# Buck_Converter.net
KiCad netlist of a schematic drawn in Altium Designer
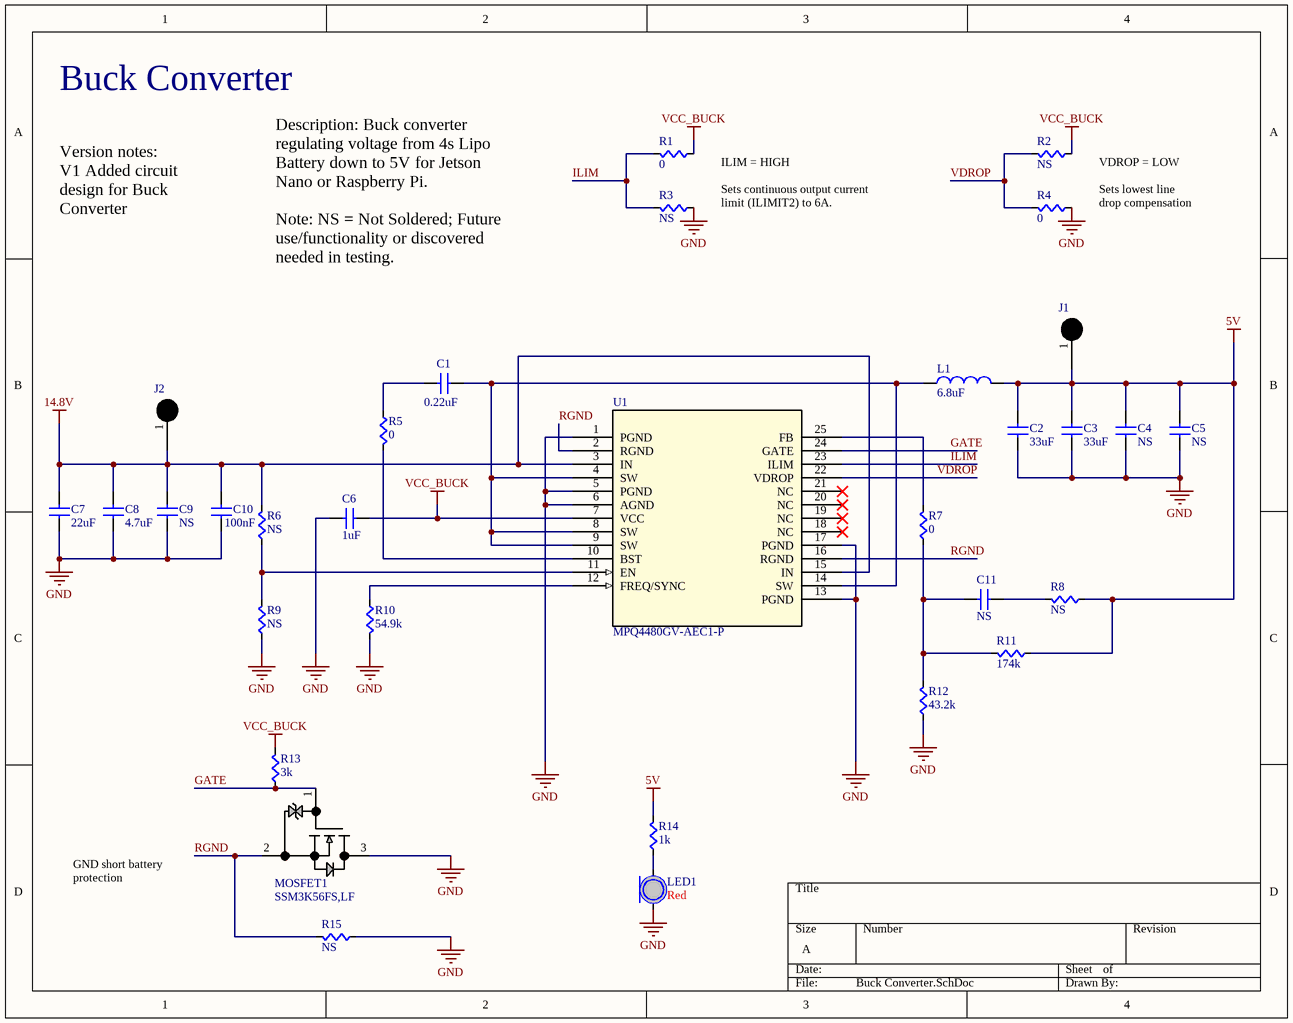
[diagram p0: Buck Converter.SchDoc]

(export (version "E")
  (design (tool "Eeschema 10.0.6"))
  (components
    (comp (ref "C1")
      (value "0.22uF")
      (footprint "CAPC0603")
      (description "0.22 µF ±10% 50V Ceramic Capacitor X7R 0603 (1608 Metric)")
      (fields (field (name "Comment") "C1608X7R1H224K080AE"))
      (libsource (lib "Passives") (part "C1608X7R1H224K080AE"))
    )
    (comp (ref "C2")
      (value "33uF")
      (footprint "CAP1210")
      (description "33 µF ±20% 10V Ceramic Capacitor X5R 1210 (3225 Metric)")
      (fields (field (name "Comment") "C3225X5R1A336M200AC"))
      (libsource (lib "Passives") (part "C3225X5R1A336M200AC"))
    )
    (comp (ref "C3")
      (value "33uF")
      (footprint "CAP1210")
      (description "33 µF ±20% 10V Ceramic Capacitor X5R 1210 (3225 Metric)")
      (fields (field (name "Comment") "C3225X5R1A336M200AC"))
      (libsource (lib "Passives") (part "C3225X5R1A336M200AC"))
    )
    (comp (ref "C4")
      (value "NS")
      (footprint "CAPC1206")
      (fields (field (name "Comment") "Cap"))
      (libsource (lib "Passives") (part "Cap"))
    )
    (comp (ref "C5")
      (value "NS")
      (footprint "CAPC1206")
      (fields (field (name "Comment") "Cap"))
      (libsource (lib "Passives") (part "Cap"))
    )
    (comp (ref "C6")
      (value "1uF")
      (footprint "CAPC0603")
      (description "1 µF ±10% 50V Ceramic Capacitor X5R 0603 (1608 Metric)")
      (fields (field (name "Comment") "CL10A105KB8NNNC"))
      (libsource (lib "Passives") (part "CL10A105KB8NNNC"))
    )
    (comp (ref "C7")
      (value "22uF")
      (footprint "CAPC1206")
      (description "22 µF ±10% 25V Ceramic Capacitor X5R 1206 (3216 Metric)")
      (fields (field (name "Comment") "CL31A226KAHNNNE"))
      (libsource (lib "Passives") (part "CL31A226KAHNNNE"))
    )
    (comp (ref "C8")
      (value "4.7uF")
      (footprint "CAPC1206")
      (description "4.7 µF ±10% 50V Ceramic Capacitor X7R 1206 (3216 Metric)")
      (fields (field (name "Comment") "885012208094"))
      (libsource (lib "Passives") (part "885012208094"))
    )
    (comp (ref "C9")
      (value "NS")
      (footprint "CAPC1206")
      (description "Not Soldered (NS)")
      (fields (field (name "Comment") "Cap"))
      (libsource (lib "Passives") (part "Cap"))
    )
    (comp (ref "C10")
      (value "100nF")
      (footprint "CAPC0603")
      (description "0.1 µF ±10% 50V Ceramic Capacitor X7R 0603 (1608 Metric)")
      (fields (field (name "Comment") "CL10B104KB8NNNC"))
      (libsource (lib "Passives") (part "CL10B104KB8NNNC"))
    )
    (comp (ref "C11")
      (value "NS")
      (footprint "CAPC0603")
      (fields (field (name "Comment") "Cap"))
      (libsource (lib "Passives") (part "Cap"))
    )
    (comp (ref "J1")
      (value "5000 Test Point")
      (footprint "5000 Test Point")
      (libsource (lib "Connectors") (part "5000 Test Point"))
    )
    (comp (ref "J2")
      (value "5000 Test Point")
      (footprint "5000 Test Point")
      (libsource (lib "Connectors") (part "5000 Test Point"))
    )
    (comp (ref "L1")
      (value "SRR1280A-6R8Y")
      (footprint "SRR1208 Series")
      (description "FIXED IND 6.8UH 7.6A 18.5MOHM SM")
      (fields (field (name "INDUCTANCE") "6.8uF"))
      (libsource (lib "Passives") (part "SRR1280A-6R8Y"))
    )
    (comp (ref "LED1")
      (value "LED")
      (footprint "LED1206")
      (fields (field (name "COLOR") "Red"))
      (libsource (lib "Semiconductors") (part "LED"))
    )
    (comp (ref "MOSFET1")
      (value "SSM3K56FS,LF")
      (footprint "SSM_TOS")
      (description "No Description Available")
      (fields (field (name "COPYRIGHT") "Copyright (C) 2023 Ultra Librarian. All rights reserved."))
      (libsource (lib "ICs") (part "SSM3K56FS,LF"))
    )
    (comp (ref "R1")
      (value "0")
      (footprint "RES0603")
      (description "0 Ohms Jumper Chip Resistor 0603 (1608 Metric) Automotive AEC-Q200 Thick Film")
      (fields (field (name "Comment") "RMCF0603ZT0R00"))
      (libsource (lib "Passives") (part "RMCF0603ZT0R00"))
    )
    (comp (ref "R2")
      (value "NS")
      (footprint "RES0603")
      (fields (field (name "Comment") "Res"))
      (libsource (lib "Passives") (part "Res"))
    )
    (comp (ref "R3")
      (value "NS")
      (footprint "RES0603")
      (fields (field (name "Comment") "Res"))
      (libsource (lib "Passives") (part "Res"))
    )
    (comp (ref "R4")
      (value "0")
      (footprint "RES0603")
      (description "0 Ohms Jumper Chip Resistor 0603 (1608 Metric) Automotive AEC-Q200 Thick Film")
      (fields (field (name "Comment") "RMCF0603ZT0R00"))
      (libsource (lib "Passives") (part "RMCF0603ZT0R00"))
    )
    (comp (ref "R5")
      (value "0")
      (footprint "RES0603")
      (description "0 Ohms Jumper Chip Resistor 0603 (1608 Metric) Automotive AEC-Q200 Thick Film")
      (fields (field (name "Comment") "RMCF0603ZT0R00"))
      (libsource (lib "Passives") (part "RMCF0603ZT0R00"))
    )
    (comp (ref "R6")
      (value "NS")
      (footprint "RES0603")
      (fields (field (name "Comment") "Res"))
      (libsource (lib "Passives") (part "Res"))
    )
    (comp (ref "R7")
      (value "0")
      (footprint "RES0603")
      (description "0 Ohms Jumper Chip Resistor 0603 (1608 Metric) Automotive AEC-Q200 Thick Film")
      (fields (field (name "Comment") "RMCF0603ZT0R00"))
      (libsource (lib "Passives") (part "RMCF0603ZT0R00"))
    )
    (comp (ref "R8")
      (value "NS")
      (footprint "RES0603")
      (fields (field (name "Comment") "Res"))
      (libsource (lib "Passives") (part "Res"))
    )
    (comp (ref "R9")
      (value "NS")
      (footprint "RES0603")
      (fields (field (name "Comment") "Res"))
      (libsource (lib "Passives") (part "Res"))
    )
    (comp (ref "R10")
      (value "54.9k")
      (footprint "RES0603")
      (description "54.9 kOhms ±1% 0.1W, 1/10W Chip Resistor 0603 (1608 Metric) Automotive AEC-Q200 Thick Film")
      (fields (field (name "Comment") "RMCF0603FT54K9"))
      (libsource (lib "Passives") (part "RMCF0603FT54K9"))
    )
    (comp (ref "R11")
      (value "174k")
      (footprint "RES0603")
      (description "174 kOhms ±1% 0.1W, 1/10W Chip Resistor 0603 (1608 Metric) Moisture Resistant Thick Film")
      (fields (field (name "Comment") "RC0603FR-07174KL"))
      (libsource (lib "Passives") (part "RC0603FR-07174KL"))
    )
    (comp (ref "R12")
      (value "43.2k")
      (footprint "RES0603")
      (description "43.2 kOhms ±1% 0.1W, 1/10W Chip Resistor 0603 (1608 Metric) Moisture Resistant Thick Film")
      (fields (field (name "Comment") "RC0603FR-0743K2L"))
      (libsource (lib "Passives") (part "RC0603FR-0743K2L"))
    )
    (comp (ref "R13")
      (value "3k")
      (footprint "RES0603")
      (description "3 kOhms ±1% 0.1W, 1/10W Chip Resistor 0603 (1608 Metric) Automotive AEC-Q200 Thick Film")
      (fields (field (name "Comment") "RMCF0603FT3K00"))
      (libsource (lib "Passives") (part "RMCF0603FT3K00"))
    )
    (comp (ref "R14")
      (value "1k")
      (footprint "RES0603")
      (description "1 kOhms ±1% 0.1W, 1/10W Chip Resistor 0603 (1608 Metric) Moisture Resistant Thick Film")
      (fields (field (name "Comment") "RC0603FR-071KL"))
      (libsource (lib "Passives") (part "RC0603FR-071KL"))
    )
    (comp (ref "R15")
      (value "NS")
      (footprint "RES0603")
      (fields (field (name "Comment") "Res"))
      (libsource (lib "Passives") (part "Res"))
    )
    (comp (ref "U1")
      (value "MPQ4480GV-AEC1-P")
      (footprint "QFN-25_4X5_MNP")
      (description "No Description Available")
      (fields (field (name "COPYRIGHT") "Copyright (C) 2023 Ultra Librarian. All rights reserved."))
      (libsource (lib "ICs") (part "MPQ4480GV-AEC1-P"))
    )
  )
  (nets
    (net (code "1") (name "/GATE") (class "Default")
      (node (ref "MOSFET1") (pin "1") (pinfunction "1_1") (pintype "passive"))
      (node (ref "R13") (pin "2") (pinfunction "B_2") (pintype "passive"))
      (node (ref "U1") (pin "24") (pinfunction "GATE_24") (pintype "passive"))
    )
    (net (code "2") (name "/ILIM") (class "Default")
      (node (ref "R1") (pin "1") (pinfunction "A_1") (pintype "passive"))
      (node (ref "R3") (pin "1") (pinfunction "A_1") (pintype "passive"))
      (node (ref "U1") (pin "23") (pinfunction "ILIM_23") (pintype "passive"))
    )
    (net (code "3") (name "/RGND") (class "Default")
      (node (ref "MOSFET1") (pin "2") (pinfunction "2_2") (pintype "passive"))
      (node (ref "R15") (pin "1") (pinfunction "A_1") (pintype "passive"))
      (node (ref "U1") (pin "16") (pinfunction "RGND_16") (pintype "passive"))
      (node (ref "U1") (pin "2") (pinfunction "RGND_2") (pintype "passive"))
    )
    (net (code "4") (name "/VDROP") (class "Default")
      (node (ref "R2") (pin "1") (pinfunction "A_1") (pintype "passive"))
      (node (ref "R4") (pin "1") (pinfunction "A_1") (pintype "passive"))
      (node (ref "U1") (pin "22") (pinfunction "VDROP_22") (pintype "power_in"))
    )
    (net (code "5") (name "5V") (class "Default")
      (node (ref "C2") (pin "1") (pinfunction "A_1") (pintype "passive"))
      (node (ref "C3") (pin "1") (pinfunction "A_1") (pintype "passive"))
      (node (ref "C4") (pin "1") (pinfunction "A_1") (pintype "passive"))
      (node (ref "C5") (pin "1") (pinfunction "A_1") (pintype "passive"))
      (node (ref "J1") (pin "1") (pintype "passive"))
      (node (ref "L1") (pin "2") (pinfunction "B_2") (pintype "passive"))
      (node (ref "R11") (pin "2") (pinfunction "B_2") (pintype "passive"))
      (node (ref "R14") (pin "1") (pinfunction "A_1") (pintype "passive"))
      (node (ref "R8") (pin "2") (pinfunction "B_2") (pintype "passive"))
    )
    (net (code "6") (name "14.8V") (class "Default")
      (node (ref "C10") (pin "1") (pinfunction "A_1") (pintype "passive"))
      (node (ref "C7") (pin "1") (pinfunction "A_1") (pintype "passive"))
      (node (ref "C8") (pin "1") (pinfunction "A_1") (pintype "passive"))
      (node (ref "C9") (pin "1") (pinfunction "A_1") (pintype "passive"))
      (node (ref "J2") (pin "1") (pintype "passive"))
      (node (ref "R6") (pin "1") (pinfunction "A_1") (pintype "passive"))
      (node (ref "U1") (pin "15") (pinfunction "IN_15") (pintype "power_in"))
      (node (ref "U1") (pin "3") (pinfunction "IN_3") (pintype "power_in"))
    )
    (net (code "7") (name "GND") (class "Default")
      (node (ref "C10") (pin "2") (pinfunction "B_2") (pintype "passive"))
      (node (ref "C2") (pin "2") (pinfunction "B_2") (pintype "passive"))
      (node (ref "C3") (pin "2") (pinfunction "B_2") (pintype "passive"))
      (node (ref "C4") (pin "2") (pinfunction "B_2") (pintype "passive"))
      (node (ref "C5") (pin "2") (pinfunction "B_2") (pintype "passive"))
      (node (ref "C6") (pin "2") (pinfunction "B_2") (pintype "passive"))
      (node (ref "C7") (pin "2") (pinfunction "B_2") (pintype "passive"))
      (node (ref "C8") (pin "2") (pinfunction "B_2") (pintype "passive"))
      (node (ref "C9") (pin "2") (pinfunction "B_2") (pintype "passive"))
      (node (ref "LED1") (pin "C") (pinfunction "C_C") (pintype "passive"))
      (node (ref "MOSFET1") (pin "3") (pinfunction "3_3") (pintype "passive"))
      (node (ref "R10") (pin "1") (pinfunction "A_1") (pintype "passive"))
      (node (ref "R12") (pin "2") (pinfunction "B_2") (pintype "passive"))
      (node (ref "R15") (pin "2") (pinfunction "B_2") (pintype "passive"))
      (node (ref "R3") (pin "2") (pinfunction "B_2") (pintype "passive"))
      (node (ref "R4") (pin "2") (pinfunction "B_2") (pintype "passive"))
      (node (ref "R9") (pin "2") (pinfunction "B_2") (pintype "passive"))
      (node (ref "U1") (pin "1") (pinfunction "PGND_1") (pintype "passive"))
      (node (ref "U1") (pin "13") (pinfunction "PGND_13") (pintype "passive"))
      (node (ref "U1") (pin "17") (pinfunction "PGND_17") (pintype "passive"))
      (node (ref "U1") (pin "5") (pinfunction "PGND_5") (pintype "passive"))
      (node (ref "U1") (pin "6") (pinfunction "AGND_6") (pintype "passive"))
    )
    (net (code "8") (name "Net-(C1-A)") (class "Default")
      (node (ref "C1") (pin "1") (pinfunction "A_1") (pintype "passive"))
      (node (ref "R5") (pin "2") (pinfunction "B_2") (pintype "passive"))
    )
    (net (code "9") (name "Net-(C1-B)") (class "Default")
      (node (ref "C1") (pin "2") (pinfunction "B_2") (pintype "passive"))
      (node (ref "L1") (pin "1") (pinfunction "A_1") (pintype "passive"))
      (node (ref "U1") (pin "14") (pinfunction "SW_14") (pintype "passive"))
      (node (ref "U1") (pin "4") (pinfunction "SW_4") (pintype "passive"))
      (node (ref "U1") (pin "8") (pinfunction "SW_8") (pintype "passive"))
      (node (ref "U1") (pin "9") (pinfunction "SW_9") (pintype "passive"))
    )
    (net (code "10") (name "Net-(C11-A)") (class "Default")
      (node (ref "C11") (pin "1") (pinfunction "A_1") (pintype "passive"))
      (node (ref "R11") (pin "1") (pinfunction "A_1") (pintype "passive"))
      (node (ref "R12") (pin "1") (pinfunction "A_1") (pintype "passive"))
      (node (ref "R7") (pin "2") (pinfunction "B_2") (pintype "passive"))
    )
    (net (code "11") (name "Net-(C11-B)") (class "Default")
      (node (ref "C11") (pin "2") (pinfunction "B_2") (pintype "passive"))
      (node (ref "R8") (pin "1") (pinfunction "A_1") (pintype "passive"))
    )
    (net (code "12") (name "Net-(R5-A)") (class "Default")
      (node (ref "R5") (pin "1") (pinfunction "A_1") (pintype "passive"))
      (node (ref "U1") (pin "10") (pinfunction "BST_10") (pintype "passive"))
    )
    (net (code "13") (name "Net-(R6-B)") (class "Default")
      (node (ref "R6") (pin "2") (pinfunction "B_2") (pintype "passive"))
      (node (ref "R9") (pin "1") (pinfunction "A_1") (pintype "passive"))
      (node (ref "U1") (pin "11") (pinfunction "EN_11") (pintype "input"))
    )
    (net (code "14") (name "Net-(R7-A)") (class "Default")
      (node (ref "R7") (pin "1") (pinfunction "A_1") (pintype "passive"))
      (node (ref "U1") (pin "25") (pinfunction "FB_25") (pintype "passive"))
    )
    (net (code "15") (name "Net-(R10-B)") (class "Default")
      (node (ref "R10") (pin "2") (pinfunction "B_2") (pintype "passive"))
      (node (ref "U1") (pin "12") (pinfunction "FREQ/SYNC_12") (pintype "input"))
    )
    (net (code "16") (name "Net-(R14-B)") (class "Default")
      (node (ref "LED1") (pin "A") (pinfunction "A_A") (pintype "passive"))
      (node (ref "R14") (pin "2") (pinfunction "B_2") (pintype "passive"))
    )
    (net (code "17") (name "VCC_BUCK") (class "Default")
      (node (ref "C6") (pin "1") (pinfunction "A_1") (pintype "passive"))
      (node (ref "R1") (pin "2") (pinfunction "B_2") (pintype "passive"))
      (node (ref "R13") (pin "1") (pinfunction "A_1") (pintype "passive"))
      (node (ref "R2") (pin "2") (pinfunction "B_2") (pintype "passive"))
      (node (ref "U1") (pin "7") (pinfunction "VCC_7") (pintype "power_in"))
    )
    (net (code "18") (name "unconnected-(U1-NC-Pad18)") (class "Default")
      (node (ref "U1") (pin "18") (pinfunction "NC_18") (pintype "passive+no_connect"))
    )
    (net (code "19") (name "unconnected-(U1-NC-Pad19)") (class "Default")
      (node (ref "U1") (pin "19") (pinfunction "NC_19") (pintype "passive+no_connect"))
    )
    (net (code "20") (name "unconnected-(U1-NC-Pad20)") (class "Default")
      (node (ref "U1") (pin "20") (pinfunction "NC_20") (pintype "passive+no_connect"))
    )
    (net (code "21") (name "unconnected-(U1-NC-Pad21)") (class "Default")
      (node (ref "U1") (pin "21") (pinfunction "NC_21") (pintype "passive+no_connect"))
    )
  )
)
